# hbridge2.net
KiCad netlist of a schematic drawn in EAGLE
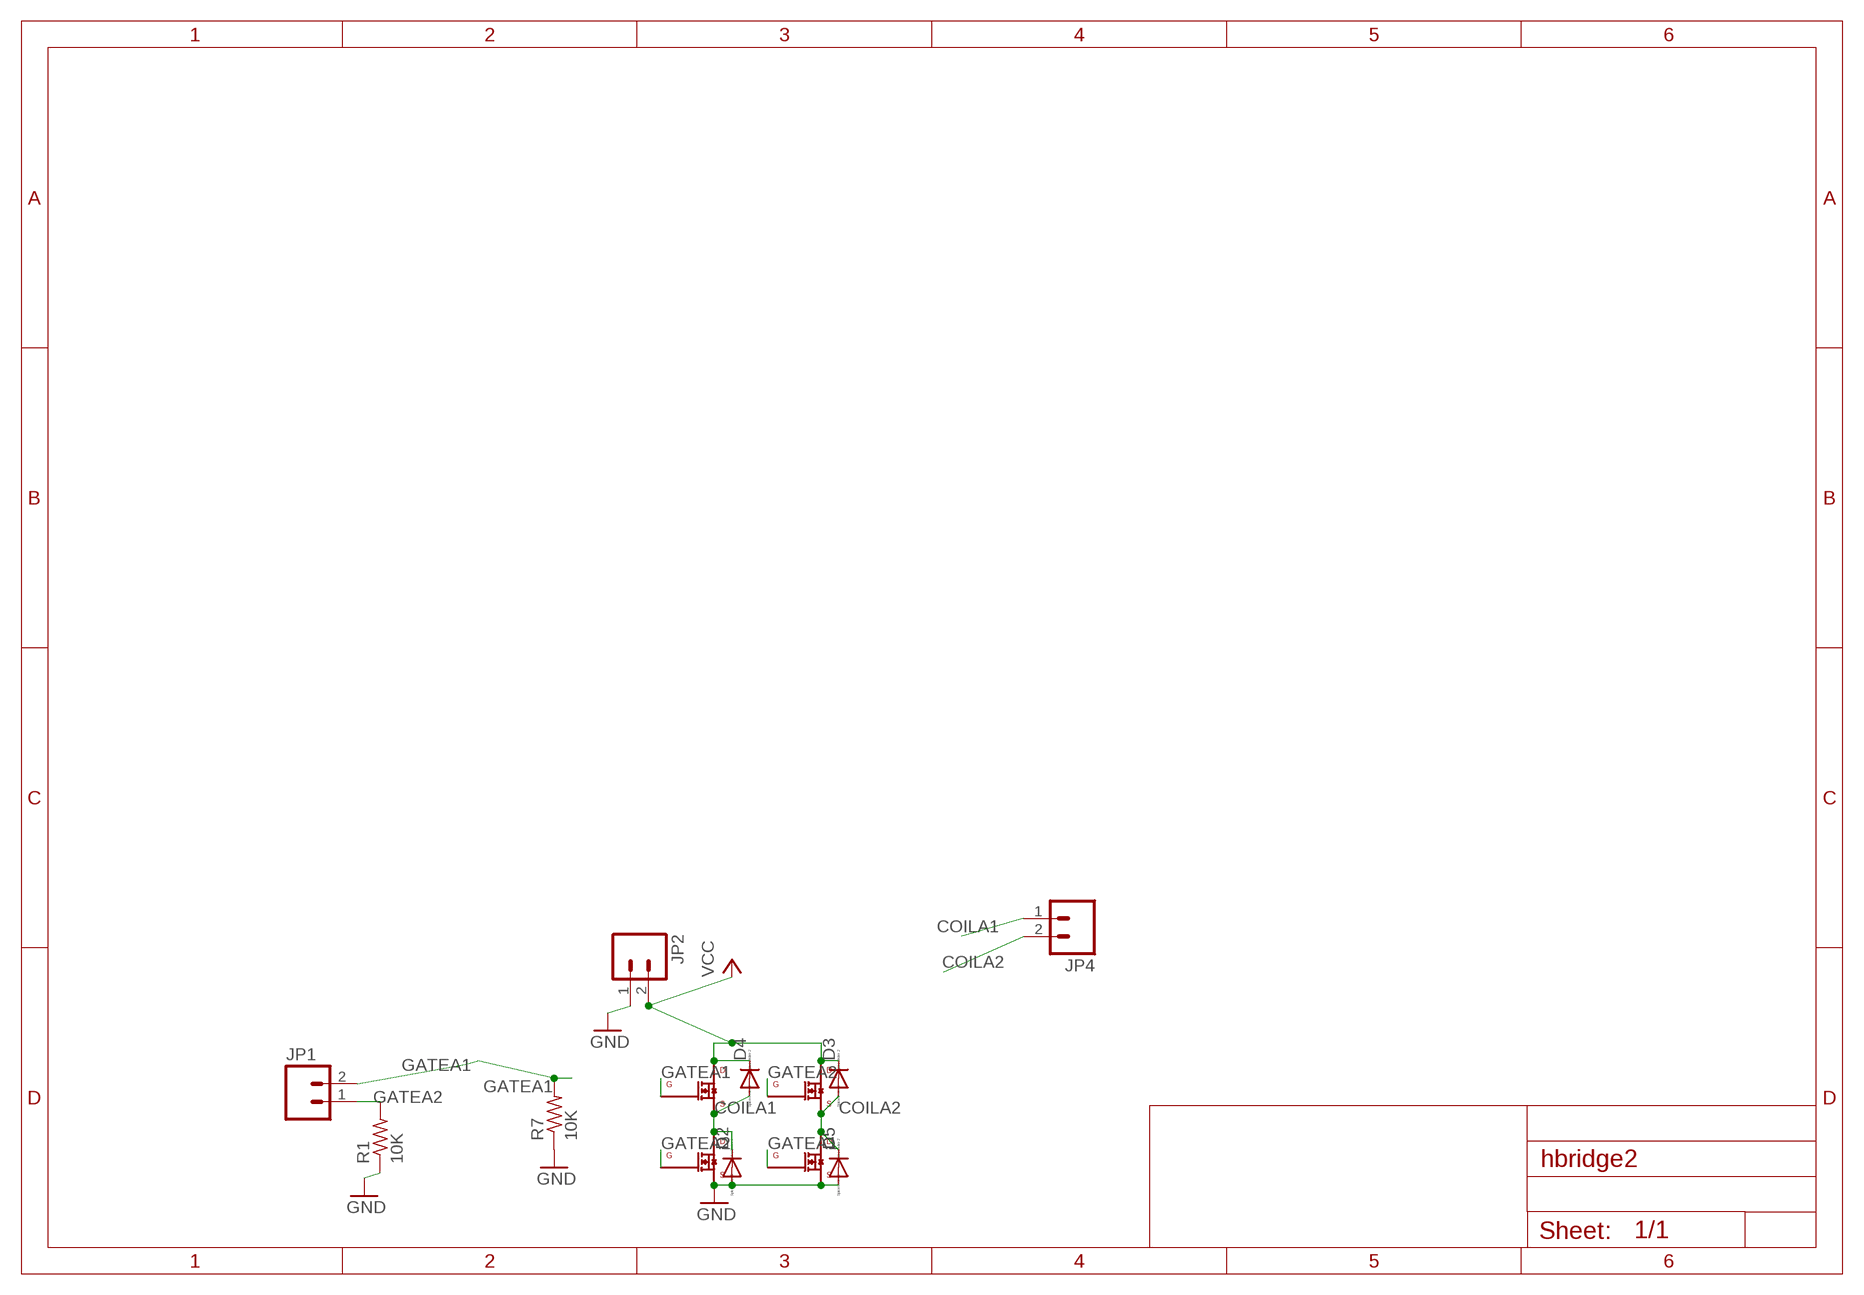
[diagram p0: schematic, sheet 1]

(export (version "E")
  (design (tool "Eeschema 10.0.6"))
  (components
    (comp (ref "D2")
      (value "DIODE-DO-214AC")
      (footprint "eagle-import:DO-214AC")
      (libsource (lib "eagle-import") (part "DIODE-DO-214AC"))
    )
    (comp (ref "D3")
      (value "DIODE-DO-214AC")
      (footprint "eagle-import:DO-214AC")
      (libsource (lib "eagle-import") (part "DIODE-DO-214AC"))
    )
    (comp (ref "D4")
      (value "DIODE-DO-214AC")
      (footprint "eagle-import:DO-214AC")
      (libsource (lib "eagle-import") (part "DIODE-DO-214AC"))
    )
    (comp (ref "D5")
      (value "DIODE-DO-214AC")
      (footprint "eagle-import:DO-214AC")
      (libsource (lib "eagle-import") (part "DIODE-DO-214AC"))
    )
    (comp (ref "JP1")
      (value "M02PTH")
      (footprint "eagle-import:1X02")
      (libsource (lib "eagle-import") (part "M02PTH"))
    )
    (comp (ref "JP2")
      (value "M02PTH")
      (footprint "eagle-import:1X02")
      (libsource (lib "eagle-import") (part "M02PTH"))
    )
    (comp (ref "JP4")
      (value "M02PTH")
      (footprint "eagle-import:1X02")
      (libsource (lib "eagle-import") (part "M02PTH"))
    )
    (comp (ref "Q2")
      (value "IRLML0060")
      (footprint "eagle-import:SOT-23")
      (libsource (lib "eagle-import") (part "IRLML0060"))
    )
    (comp (ref "Q3")
      (value "IRLML0060")
      (footprint "eagle-import:SOT-23")
      (libsource (lib "eagle-import") (part "IRLML0060"))
    )
    (comp (ref "Q4")
      (value "IRLML0060")
      (footprint "eagle-import:SOT-23")
      (libsource (lib "eagle-import") (part "IRLML0060"))
    )
    (comp (ref "Q5")
      (value "IRLML0060")
      (footprint "eagle-import:SOT-23")
      (libsource (lib "eagle-import") (part "IRLML0060"))
    )
    (comp (ref "R1")
      (value "10K")
      (footprint "eagle-import:R0603")
      (libsource (lib "eagle-import") (part "R-US_R0603"))
    )
    (comp (ref "R7")
      (value "10K")
      (footprint "eagle-import:R0603")
      (libsource (lib "eagle-import") (part "R-US_R0603"))
    )
  )
  (nets
    (net (code "1") (name "/COILA1") (class "Default")
      (node (ref "D2") (pin "C") (pinfunction "C_C") (pintype "passive"))
      (node (ref "D4") (pin "A") (pinfunction "A_A") (pintype "passive"))
      (node (ref "JP4") (pin "1") (pinfunction "1_1") (pintype "passive"))
      (node (ref "Q2") (pin "3") (pinfunction "DRAIN_3") (pintype "bidirectional"))
      (node (ref "Q4") (pin "2") (pinfunction "SOURCE_2") (pintype "bidirectional"))
    )
    (net (code "2") (name "/COILA2") (class "Default")
      (node (ref "D3") (pin "A") (pinfunction "A_A") (pintype "passive"))
      (node (ref "D5") (pin "C") (pinfunction "C_C") (pintype "passive"))
      (node (ref "JP4") (pin "2") (pinfunction "2_2") (pintype "passive"))
      (node (ref "Q3") (pin "2") (pinfunction "SOURCE_2") (pintype "bidirectional"))
      (node (ref "Q5") (pin "3") (pinfunction "DRAIN_3") (pintype "bidirectional"))
    )
    (net (code "3") (name "/GATEA1") (class "Default")
      (node (ref "JP1") (pin "2") (pinfunction "2_2") (pintype "passive"))
      (node (ref "Q4") (pin "1") (pinfunction "GATE_1") (pintype "bidirectional"))
      (node (ref "Q5") (pin "1") (pinfunction "GATE_1") (pintype "bidirectional"))
      (node (ref "R7") (pin "2") (pinfunction "2_2") (pintype "passive"))
    )
    (net (code "4") (name "/GATEA2") (class "Default")
      (node (ref "JP1") (pin "1") (pinfunction "1_1") (pintype "passive"))
      (node (ref "Q2") (pin "1") (pinfunction "GATE_1") (pintype "bidirectional"))
      (node (ref "Q3") (pin "1") (pinfunction "GATE_1") (pintype "bidirectional"))
      (node (ref "R1") (pin "2") (pinfunction "2_2") (pintype "passive"))
    )
    (net (code "5") (name "GND") (class "Default")
      (node (ref "D2") (pin "A") (pinfunction "A_A") (pintype "passive"))
      (node (ref "D5") (pin "A") (pinfunction "A_A") (pintype "passive"))
      (node (ref "JP2") (pin "1") (pinfunction "1_1") (pintype "passive"))
      (node (ref "Q2") (pin "2") (pinfunction "SOURCE_2") (pintype "bidirectional"))
      (node (ref "Q5") (pin "2") (pinfunction "SOURCE_2") (pintype "bidirectional"))
      (node (ref "R1") (pin "1") (pinfunction "1_1") (pintype "passive"))
      (node (ref "R7") (pin "1") (pinfunction "1_1") (pintype "passive"))
    )
    (net (code "6") (name "VCC") (class "Default")
      (node (ref "D3") (pin "C") (pinfunction "C_C") (pintype "passive"))
      (node (ref "D4") (pin "C") (pinfunction "C_C") (pintype "passive"))
      (node (ref "JP2") (pin "2") (pinfunction "2_2") (pintype "passive"))
      (node (ref "Q3") (pin "3") (pinfunction "DRAIN_3") (pintype "bidirectional"))
      (node (ref "Q4") (pin "3") (pinfunction "DRAIN_3") (pintype "bidirectional"))
    )
  )
)
